# COMS0010_Comms_Test_Board.net
KiCad netlist of a schematic drawn in Altium Designer
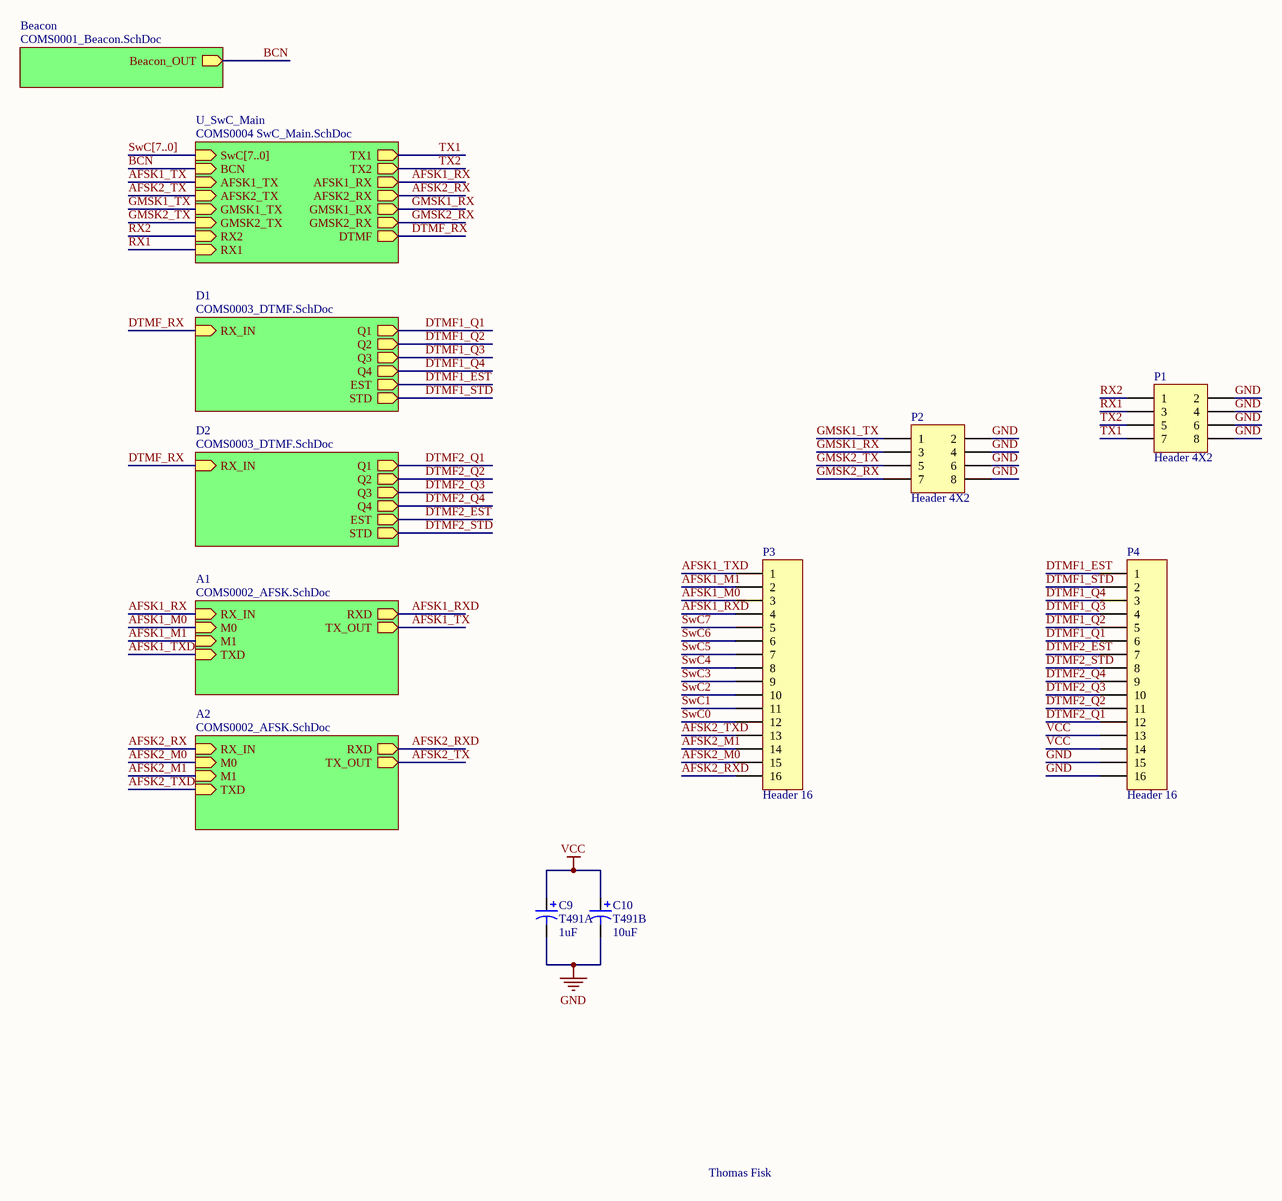
[diagram p0: COMS0010_Comms_Test_Board.SchDoc]

(export (version "E")
  (design (tool "Eeschema 10.0.6"))
  (components
    (comp (ref "C9")
      (value "T491A")
      (footprint "A")
      (description "Solid Tantalum Chip Capacitor, Standard T491 Series - Industrial Grade")
      (fields (field (name "ALTIUM_VALUE") "1uF") (field (name "PUBLISHER") "Altium Limited"))
      (libsource (lib "KEMET Chip Capacitor") (part "T491A"))
    )
    (comp (ref "C10")
      (value "T491B")
      (footprint "B")
      (description "Solid Tantalum Chip Capacitor, Standard T491 Series - Industrial Grade")
      (fields (field (name "ALTIUM_VALUE") "10uF") (field (name "PUBLISHER") "Altium Limited"))
      (libsource (lib "KEMET Chip Capacitor") (part "T491B"))
    )
    (comp (ref "P1")
      (value "Header 4X2")
      (footprint "HDR2X4")
      (description "Header, 4-Pin, Dual row")
      (fields (field (name "PUBLISHER") "Altium Limited"))
      (libsource (lib "Miscellaneous Connectors") (part "Header 4X2"))
    )
    (comp (ref "P2")
      (value "Header 4X2")
      (footprint "HDR2X4")
      (description "Header, 4-Pin, Dual row")
      (fields (field (name "PUBLISHER") "Altium Limited"))
      (libsource (lib "Miscellaneous Connectors") (part "Header 4X2"))
    )
    (comp (ref "P3")
      (value "Header 16")
      (footprint "HDR1X16")
      (description "Header, 16-Pin")
      (fields (field (name "PUBLISHER") "Altium Limited"))
      (libsource (lib "Miscellaneous Connectors") (part "Header 16"))
    )
    (comp (ref "P4")
      (value "Header 16")
      (footprint "HDR1X16")
      (description "Header, 16-Pin")
      (fields (field (name "PUBLISHER") "Altium Limited"))
      (libsource (lib "Miscellaneous Connectors") (part "Header 16"))
    )
  )
  (nets
    (net (code "1") (name "/AFSK1_M0") (class "Default")
      (node (ref "P3") (pin "3") (pinfunction "3_3") (pintype "passive"))
    )
    (net (code "2") (name "/AFSK1_M1") (class "Default")
      (node (ref "P3") (pin "2") (pinfunction "2_2") (pintype "passive"))
    )
    (net (code "4") (name "/AFSK1_RXD") (class "Default")
      (node (ref "P3") (pin "4") (pinfunction "4_4") (pintype "passive"))
    )
    (net (code "6") (name "/AFSK1_TXD") (class "Default")
      (node (ref "P3") (pin "1") (pinfunction "1_1") (pintype "passive"))
    )
    (net (code "7") (name "/AFSK2_M0") (class "Default")
      (node (ref "P3") (pin "15") (pinfunction "15_15") (pintype "passive"))
    )
    (net (code "8") (name "/AFSK2_M1") (class "Default")
      (node (ref "P3") (pin "14") (pinfunction "14_14") (pintype "passive"))
    )
    (net (code "10") (name "/AFSK2_RXD") (class "Default")
      (node (ref "P3") (pin "16") (pinfunction "16_16") (pintype "passive"))
    )
    (net (code "12") (name "/AFSK2_TXD") (class "Default")
      (node (ref "P3") (pin "13") (pinfunction "13_13") (pintype "passive"))
    )
    (net (code "14") (name "/DTMF1_EST") (class "Default")
      (node (ref "P4") (pin "1") (pinfunction "1_1") (pintype "passive"))
    )
    (net (code "15") (name "/DTMF1_Q1") (class "Default")
      (node (ref "P4") (pin "6") (pinfunction "6_6") (pintype "passive"))
    )
    (net (code "16") (name "/DTMF1_Q2") (class "Default")
      (node (ref "P4") (pin "5") (pinfunction "5_5") (pintype "passive"))
    )
    (net (code "17") (name "/DTMF1_Q3") (class "Default")
      (node (ref "P4") (pin "4") (pinfunction "4_4") (pintype "passive"))
    )
    (net (code "18") (name "/DTMF1_Q4") (class "Default")
      (node (ref "P4") (pin "3") (pinfunction "3_3") (pintype "passive"))
    )
    (net (code "19") (name "/DTMF1_STD") (class "Default")
      (node (ref "P4") (pin "2") (pinfunction "2_2") (pintype "passive"))
    )
    (net (code "20") (name "/DTMF2_EST") (class "Default")
      (node (ref "P4") (pin "7") (pinfunction "7_7") (pintype "passive"))
    )
    (net (code "21") (name "/DTMF2_Q1") (class "Default")
      (node (ref "P4") (pin "12") (pinfunction "12_12") (pintype "passive"))
    )
    (net (code "22") (name "/DTMF2_Q2") (class "Default")
      (node (ref "P4") (pin "11") (pinfunction "11_11") (pintype "passive"))
    )
    (net (code "23") (name "/DTMF2_Q3") (class "Default")
      (node (ref "P4") (pin "10") (pinfunction "10_10") (pintype "passive"))
    )
    (net (code "24") (name "/DTMF2_Q4") (class "Default")
      (node (ref "P4") (pin "9") (pinfunction "9_9") (pintype "passive"))
    )
    (net (code "25") (name "/DTMF2_STD") (class "Default")
      (node (ref "P4") (pin "8") (pinfunction "8_8") (pintype "passive"))
    )
    (net (code "27") (name "/GMSK1_RX") (class "Default")
      (node (ref "P2") (pin "3") (pinfunction "3_3") (pintype "passive"))
    )
    (net (code "28") (name "/GMSK1_TX") (class "Default")
      (node (ref "P2") (pin "1") (pinfunction "1_1") (pintype "passive"))
    )
    (net (code "29") (name "/GMSK2_RX") (class "Default")
      (node (ref "P2") (pin "7") (pinfunction "7_7") (pintype "passive"))
    )
    (net (code "30") (name "/GMSK2_TX") (class "Default")
      (node (ref "P2") (pin "5") (pinfunction "5_5") (pintype "passive"))
    )
    (net (code "31") (name "/RX1") (class "Default")
      (node (ref "P1") (pin "3") (pinfunction "3_3") (pintype "passive"))
    )
    (net (code "32") (name "/RX2") (class "Default")
      (node (ref "P1") (pin "1") (pinfunction "1_1") (pintype "passive"))
    )
    (net (code "33") (name "/SwC0") (class "Default")
      (node (ref "P3") (pin "12") (pinfunction "12_12") (pintype "passive"))
    )
    (net (code "34") (name "/SwC1") (class "Default")
      (node (ref "P3") (pin "11") (pinfunction "11_11") (pintype "passive"))
    )
    (net (code "35") (name "/SwC2") (class "Default")
      (node (ref "P3") (pin "10") (pinfunction "10_10") (pintype "passive"))
    )
    (net (code "36") (name "/SwC3") (class "Default")
      (node (ref "P3") (pin "9") (pinfunction "9_9") (pintype "passive"))
    )
    (net (code "37") (name "/SwC4") (class "Default")
      (node (ref "P3") (pin "8") (pinfunction "8_8") (pintype "passive"))
    )
    (net (code "38") (name "/SwC5") (class "Default")
      (node (ref "P3") (pin "7") (pinfunction "7_7") (pintype "passive"))
    )
    (net (code "39") (name "/SwC6") (class "Default")
      (node (ref "P3") (pin "6") (pinfunction "6_6") (pintype "passive"))
    )
    (net (code "40") (name "/SwC7") (class "Default")
      (node (ref "P3") (pin "5") (pinfunction "5_5") (pintype "passive"))
    )
    (net (code "42") (name "/TX1") (class "Default")
      (node (ref "P1") (pin "7") (pinfunction "7_7") (pintype "passive"))
    )
    (net (code "43") (name "/TX2") (class "Default")
      (node (ref "P1") (pin "5") (pinfunction "5_5") (pintype "passive"))
    )
    (net (code "44") (name "GND") (class "Default")
      (node (ref "C10") (pin "2") (pinfunction "2_2") (pintype "passive"))
      (node (ref "C9") (pin "2") (pinfunction "2_2") (pintype "passive"))
      (node (ref "P1") (pin "2") (pinfunction "2_2") (pintype "passive"))
      (node (ref "P1") (pin "4") (pinfunction "4_4") (pintype "passive"))
      (node (ref "P1") (pin "6") (pinfunction "6_6") (pintype "passive"))
      (node (ref "P1") (pin "8") (pinfunction "8_8") (pintype "passive"))
      (node (ref "P2") (pin "2") (pinfunction "2_2") (pintype "passive"))
      (node (ref "P2") (pin "4") (pinfunction "4_4") (pintype "passive"))
      (node (ref "P2") (pin "6") (pinfunction "6_6") (pintype "passive"))
      (node (ref "P2") (pin "8") (pinfunction "8_8") (pintype "passive"))
      (node (ref "P4") (pin "15") (pinfunction "15_15") (pintype "passive"))
      (node (ref "P4") (pin "16") (pinfunction "16_16") (pintype "passive"))
    )
    (net (code "45") (name "VCC") (class "Default")
      (node (ref "C10") (pin "1") (pinfunction "1_1") (pintype "passive"))
      (node (ref "C9") (pin "1") (pinfunction "1_1") (pintype "passive"))
      (node (ref "P4") (pin "13") (pinfunction "13_13") (pintype "passive"))
      (node (ref "P4") (pin "14") (pinfunction "14_14") (pintype "passive"))
    )
  )
)
